# rapidshark_mark_6_11.net
KiCad netlist of a schematic drawn in EAGLE
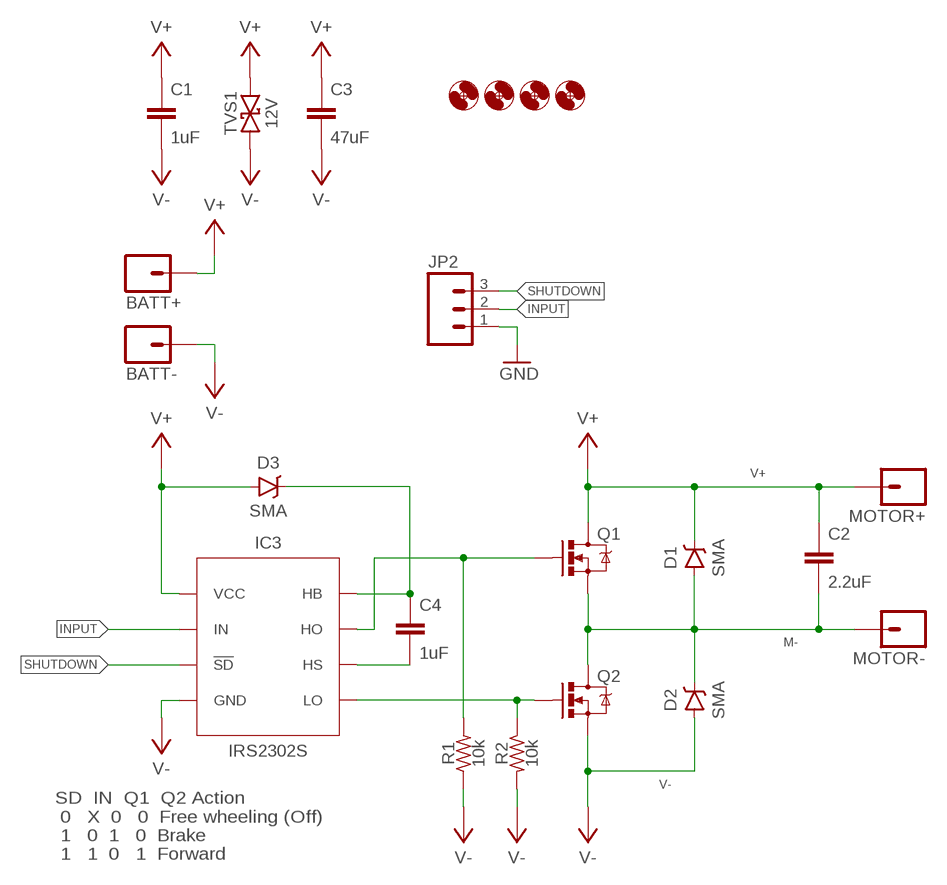
[diagram p0: schematic, sheet 1]

(export (version "E")
  (design (tool "Eeschema 10.0.6"))
  (components
    (comp (ref "BATT+")
      (value "M01PTH_2MM")
      (footprint "eagle-import:1X01_2MM")
      (libsource (lib "eagle-import") (part "M01PTH_2MM"))
    )
    (comp (ref "BATT-")
      (value "M01PTH_2MM")
      (footprint "eagle-import:1X01_2MM")
      (libsource (lib "eagle-import") (part "M01PTH_2MM"))
    )
    (comp (ref "C1")
      (value "1uF")
      (footprint "eagle-import:C0805")
      (libsource (lib "eagle-import") (part "CAPACITOR-CERAMICC0805"))
    )
    (comp (ref "C2")
      (value "2.2uF")
      (footprint "eagle-import:C0805")
      (libsource (lib "eagle-import") (part "CAPACITOR-CERAMICC0805"))
    )
    (comp (ref "C3")
      (value "47uF")
      (footprint "eagle-import:C1206")
      (libsource (lib "eagle-import") (part "CAPACITOR-CERAMICC1206"))
    )
    (comp (ref "C4")
      (value "1uF")
      (footprint "eagle-import:C0805")
      (libsource (lib "eagle-import") (part "CAPACITOR-CERAMICC0805"))
    )
    (comp (ref "D1")
      (value "SMA")
      (footprint "eagle-import:SMA-DIODE-SCHOTTKY")
      (libsource (lib "eagle-import") (part "DIODE-SCHOTTKYSMA"))
    )
    (comp (ref "D2")
      (value "SMA")
      (footprint "eagle-import:SMA-DIODE-SCHOTTKY")
      (libsource (lib "eagle-import") (part "DIODE-SCHOTTKYSMA"))
    )
    (comp (ref "D3")
      (value "SMA")
      (footprint "eagle-import:SMA-DIODE-SCHOTTKY")
      (libsource (lib "eagle-import") (part "DIODE-SCHOTTKYSMA"))
    )
    (comp (ref "H1")
      (value "HOLE#2")
      (footprint "eagle-import:HOLE-#2")
      (libsource (lib "eagle-import") (part "HOLE#2"))
    )
    (comp (ref "H2")
      (value "HOLE#2")
      (footprint "eagle-import:HOLE-#2")
      (libsource (lib "eagle-import") (part "HOLE#2"))
    )
    (comp (ref "H3")
      (value "HOLE#2")
      (footprint "eagle-import:HOLE-#2")
      (libsource (lib "eagle-import") (part "HOLE#2"))
    )
    (comp (ref "H4")
      (value "HOLE#2")
      (footprint "eagle-import:HOLE-#2")
      (libsource (lib "eagle-import") (part "HOLE#2"))
    )
    (comp (ref "IC3")
      (value "IRS2302S")
      (footprint "eagle-import:SO08")
      (libsource (lib "eagle-import") (part "IRS2302S"))
    )
    (comp (ref "JP2")
      (value "M03JST-PTH")
      (footprint "eagle-import:JST-3-PH-RA-PTH")
      (libsource (lib "eagle-import") (part "M03JST-PTH"))
    )
    (comp (ref "MOTOR+")
      (value "M01PTH_2MM")
      (footprint "eagle-import:1X01_2MM")
      (libsource (lib "eagle-import") (part "M01PTH_2MM"))
    )
    (comp (ref "MOTOR-")
      (value "M01PTH_2MM")
      (footprint "eagle-import:1X01_2MM")
      (libsource (lib "eagle-import") (part "M01PTH_2MM"))
    )
    (comp (ref "Q1")
      (value "MOSFET-NCHANNELPSMN4R0-30YLD")
      (footprint "eagle-import:LFPAK56")
      (libsource (lib "eagle-import") (part "MOSFET-NCHANNELPSMN4R0-30YLD"))
    )
    (comp (ref "Q2")
      (value "MOSFET-NCHANNELPSMN4R0-30YLD")
      (footprint "eagle-import:LFPAK56")
      (libsource (lib "eagle-import") (part "MOSFET-NCHANNELPSMN4R0-30YLD"))
    )
    (comp (ref "R1")
      (value "10k")
      (footprint "eagle-import:R0805")
      (libsource (lib "eagle-import") (part "RESISTORR0805"))
    )
    (comp (ref "R2")
      (value "10k")
      (footprint "eagle-import:R0805")
      (libsource (lib "eagle-import") (part "RESISTORR0805"))
    )
    (comp (ref "TVS1")
      (value "12V")
      (footprint "eagle-import:DO-41-TVS-BI-10.16MM")
      (libsource (lib "eagle-import") (part "TVSDO-41-10.16MM"))
    )
  )
  (nets
    (net (code "1") (name "/M-") (class "Default")
      (node (ref "C2") (pin "2") (pinfunction "2_2") (pintype "passive"))
      (node (ref "D1") (pin "A") (pinfunction "A_A") (pintype "passive"))
      (node (ref "D2") (pin "C") (pinfunction "C_C") (pintype "passive"))
      (node (ref "MOTOR-") (pin "1") (pinfunction "1_1") (pintype "passive"))
      (node (ref "Q1") (pin "1") (pinfunction "S_1") (pintype "passive"))
      (node (ref "Q1") (pin "2") (pinfunction "S_2") (pintype "passive"))
      (node (ref "Q1") (pin "3") (pinfunction "S_3") (pintype "passive"))
      (node (ref "Q2") (pin "MB@1") (pinfunction "D_MB@1") (pintype "passive"))
      (node (ref "Q2") (pin "MB@2") (pinfunction "D_MB@2") (pintype "passive"))
    )
    (net (code "2") (name "GND") (class "Default")
      (node (ref "JP2") (pin "1") (pinfunction "1_1") (pintype "passive"))
    )
    (net (code "3") (name "INPUT") (class "Default")
      (node (ref "IC3") (pin "2") (pinfunction "IN_2") (pintype "passive"))
      (node (ref "JP2") (pin "2") (pinfunction "2_2") (pintype "passive"))
    )
    (net (code "4") (name "Net-(IC3-HB)") (class "Default")
      (node (ref "C4") (pin "1") (pinfunction "1_1") (pintype "passive"))
      (node (ref "D3") (pin "C") (pinfunction "C_C") (pintype "passive"))
      (node (ref "IC3") (pin "8") (pinfunction "HB_8") (pintype "passive"))
    )
    (net (code "5") (name "Net-(IC3-HO)") (class "Default")
      (node (ref "IC3") (pin "7") (pinfunction "HO_7") (pintype "passive"))
      (node (ref "Q1") (pin "4") (pinfunction "G_4") (pintype "passive"))
      (node (ref "R1") (pin "2") (pinfunction "2_2") (pintype "passive"))
    )
    (net (code "6") (name "Net-(IC3-HS)") (class "Default")
      (node (ref "C4") (pin "2") (pinfunction "2_2") (pintype "passive"))
      (node (ref "IC3") (pin "6") (pinfunction "HS_6") (pintype "passive"))
    )
    (net (code "7") (name "Net-(IC3-LO)") (class "Default")
      (node (ref "IC3") (pin "5") (pinfunction "LO_5") (pintype "passive"))
      (node (ref "Q2") (pin "4") (pinfunction "G_4") (pintype "passive"))
      (node (ref "R2") (pin "1") (pinfunction "1_1") (pintype "passive"))
    )
    (net (code "8") (name "SHUTDOWN") (class "Default")
      (node (ref "IC3") (pin "3") (pinfunction "~{SD}_3") (pintype "passive"))
      (node (ref "JP2") (pin "3") (pinfunction "3_3") (pintype "passive"))
    )
    (net (code "9") (name "V+") (class "Default")
      (node (ref "BATT+") (pin "1") (pinfunction "1_1") (pintype "passive"))
      (node (ref "C1") (pin "1") (pinfunction "1_1") (pintype "passive"))
      (node (ref "C2") (pin "1") (pinfunction "1_1") (pintype "passive"))
      (node (ref "C3") (pin "1") (pinfunction "1_1") (pintype "passive"))
      (node (ref "D1") (pin "C") (pinfunction "C_C") (pintype "passive"))
      (node (ref "D3") (pin "A") (pinfunction "A_A") (pintype "passive"))
      (node (ref "IC3") (pin "1") (pinfunction "VCC_1") (pintype "passive"))
      (node (ref "MOTOR+") (pin "1") (pinfunction "1_1") (pintype "passive"))
      (node (ref "Q1") (pin "MB@1") (pinfunction "D_MB@1") (pintype "passive"))
      (node (ref "Q1") (pin "MB@2") (pinfunction "D_MB@2") (pintype "passive"))
      (node (ref "TVS1") (pin "P$1") (pinfunction "1_P$1") (pintype "passive"))
    )
    (net (code "10") (name "V-") (class "Default")
      (node (ref "BATT-") (pin "1") (pinfunction "1_1") (pintype "passive"))
      (node (ref "C1") (pin "2") (pinfunction "2_2") (pintype "passive"))
      (node (ref "C3") (pin "2") (pinfunction "2_2") (pintype "passive"))
      (node (ref "D2") (pin "A") (pinfunction "A_A") (pintype "passive"))
      (node (ref "IC3") (pin "4") (pinfunction "GND_4") (pintype "passive"))
      (node (ref "Q2") (pin "1") (pinfunction "S_1") (pintype "passive"))
      (node (ref "Q2") (pin "2") (pinfunction "S_2") (pintype "passive"))
      (node (ref "Q2") (pin "3") (pinfunction "S_3") (pintype "passive"))
      (node (ref "R1") (pin "1") (pinfunction "1_1") (pintype "passive"))
      (node (ref "R2") (pin "2") (pinfunction "2_2") (pintype "passive"))
      (node (ref "TVS1") (pin "P$2") (pinfunction "2_P$2") (pintype "passive"))
    )
  )
)
